# Sheet1.net
KiCad netlist of a schematic drawn in Altium Designer
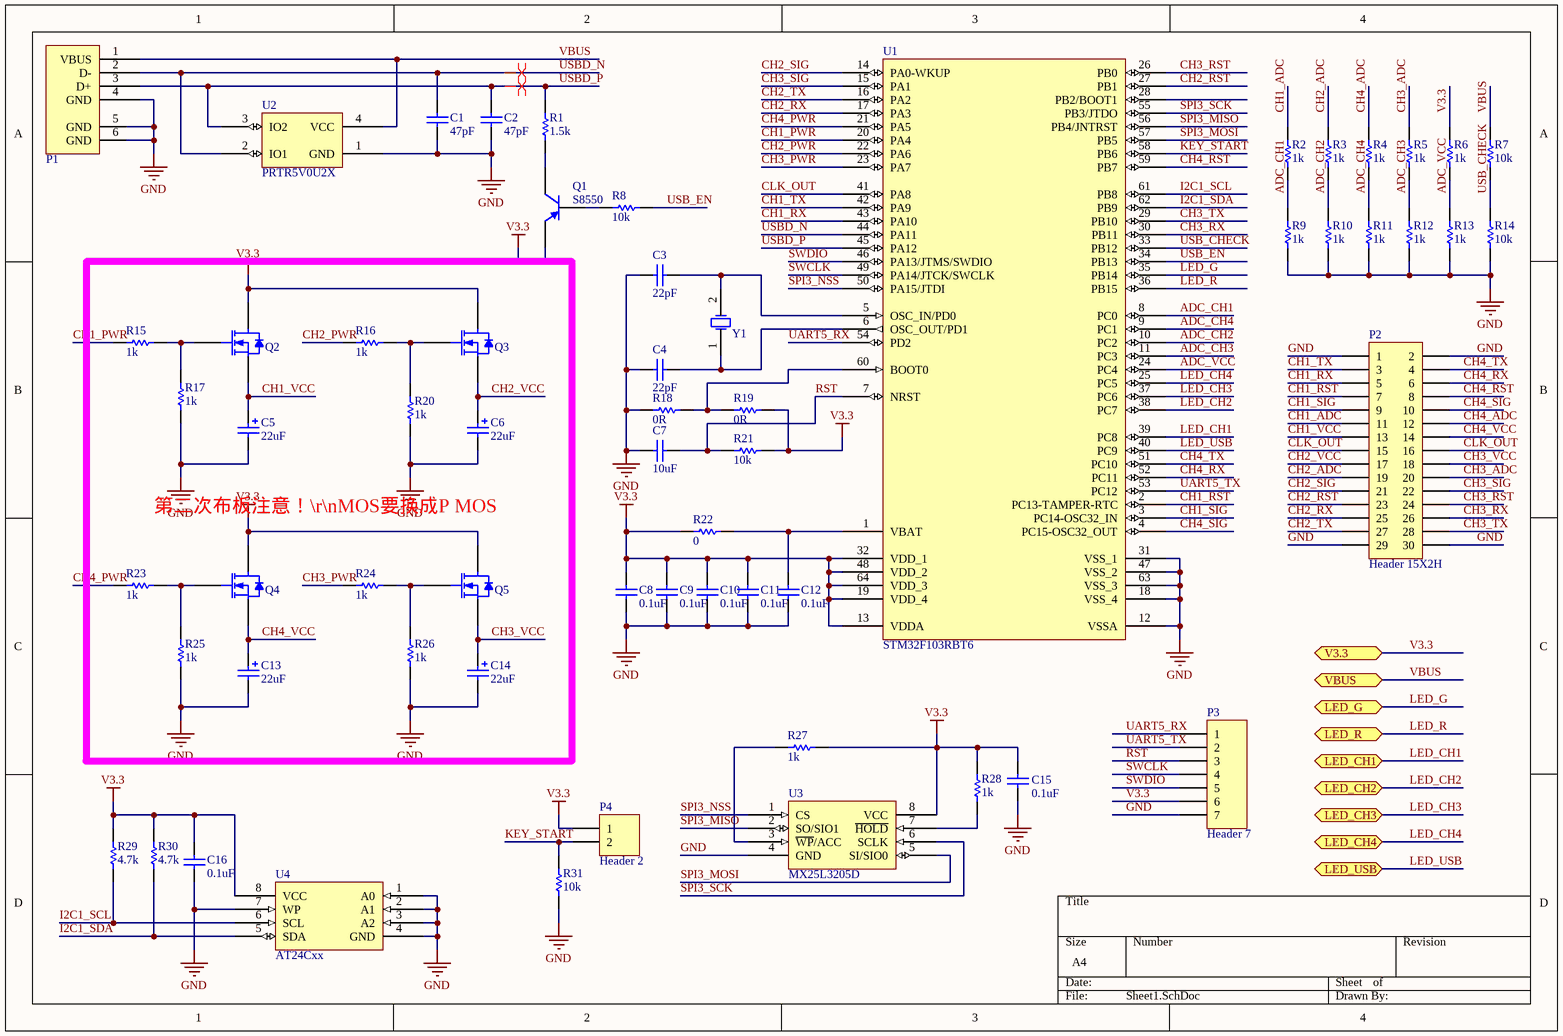
[diagram p0: Sheet1.SchDoc]

(export (version "E")
  (design (tool "Eeschema 10.0.6"))
  (components
    (comp (ref "C1")
      (value "47pF")
      (footprint "0805")
      (fields (field (name "Comment") "Cap"))
      (libsource (lib "SelfLib") (part "Cap"))
    )
    (comp (ref "C2")
      (value "47pF")
      (footprint "0805")
      (fields (field (name "Comment") "Cap"))
      (libsource (lib "SelfLib") (part "Cap"))
    )
    (comp (ref "C3")
      (value "22pF")
      (footprint "0805")
      (fields (field (name "Comment") "Cap"))
      (libsource (lib "SelfLib") (part "Cap"))
    )
    (comp (ref "C4")
      (value "22pF")
      (footprint "0805")
      (fields (field (name "Comment") "Cap"))
      (libsource (lib "SelfLib") (part "Cap"))
    )
    (comp (ref "C5")
      (value "22uF")
      (footprint "0805A")
      (fields (field (name "Comment") "Cap"))
      (libsource (lib "SelfLib") (part "Cap Pol"))
    )
    (comp (ref "C6")
      (value "22uF")
      (footprint "0805A")
      (fields (field (name "Comment") "Cap"))
      (libsource (lib "SelfLib") (part "Cap Pol"))
    )
    (comp (ref "C7")
      (value "10uF")
      (footprint "0805")
      (fields (field (name "Comment") "Cap"))
      (libsource (lib "SelfLib") (part "Cap"))
    )
    (comp (ref "C8")
      (value "0.1uF")
      (footprint "0805")
      (fields (field (name "Comment") "Cap"))
      (libsource (lib "SelfLib") (part "Cap"))
    )
    (comp (ref "C9")
      (value "0.1uF")
      (footprint "0805")
      (fields (field (name "Comment") "Cap"))
      (libsource (lib "SelfLib") (part "Cap"))
    )
    (comp (ref "C10")
      (value "0.1uF")
      (footprint "0805")
      (fields (field (name "Comment") "Cap"))
      (libsource (lib "SelfLib") (part "Cap"))
    )
    (comp (ref "C11")
      (value "0.1uF")
      (footprint "0805")
      (fields (field (name "Comment") "Cap"))
      (libsource (lib "SelfLib") (part "Cap"))
    )
    (comp (ref "C12")
      (value "0.1uF")
      (footprint "0805")
      (fields (field (name "Comment") "Cap"))
      (libsource (lib "SelfLib") (part "Cap"))
    )
    (comp (ref "C13")
      (value "22uF")
      (footprint "0805A")
      (fields (field (name "Comment") "Cap"))
      (libsource (lib "SelfLib") (part "Cap Pol"))
    )
    (comp (ref "C14")
      (value "22uF")
      (footprint "0805A")
      (fields (field (name "Comment") "Cap"))
      (libsource (lib "SelfLib") (part "Cap Pol"))
    )
    (comp (ref "C15")
      (value "0.1uF")
      (footprint "0805")
      (fields (field (name "Comment") "Cap"))
      (libsource (lib "SelfLib") (part "Cap"))
    )
    (comp (ref "C16")
      (value "0.1uF")
      (footprint "0805")
      (fields (field (name "Comment") "Cap"))
      (libsource (lib "SelfLib") (part "Cap"))
    )
    (comp (ref "P1") (value "USB") (footprint "USB_B_FE") (libsource (lib "SelfLib") (part "USB Socket")))
    (comp (ref "P2")
      (value "Header 15X2H")
      (footprint "HDR2X15H")
      (description "Header, 15-Pin, Dual row, Right Angle")
      (fields (field (name "PUBLISHER") "Altium Limited"))
      (libsource (lib "Miscellaneous Connectors") (part "Header 15X2H"))
    )
    (comp (ref "P3")
      (value "Header 7")
      (footprint "HDR1X7")
      (description "Header, 7-Pin")
      (fields (field (name "PUBLISHER") "Altium Limited"))
      (libsource (lib "Miscellaneous Connectors") (part "Header 7"))
    )
    (comp (ref "P4")
      (value "Header 2")
      (footprint "HDR1X2")
      (description "Header, 2-Pin")
      (fields (field (name "PUBLISHER") "Altium Limited"))
      (libsource (lib "Miscellaneous Connectors") (part "Header 2"))
    )
    (comp (ref "Q1") (value "S8550") (footprint "SOT-23") (libsource (lib "SelfLib") (part "S8550")))
    (comp (ref "Q2") (value "N-MOS") (footprint "SOT-23") (libsource (lib "SelfLib") (part "N-MOS")))
    (comp (ref "Q3") (value "N-MOS") (footprint "SOT-23") (libsource (lib "SelfLib") (part "N-MOS")))
    (comp (ref "Q4") (value "N-MOS") (footprint "SOT-23") (libsource (lib "SelfLib") (part "N-MOS")))
    (comp (ref "Q5") (value "N-MOS") (footprint "SOT-23") (libsource (lib "SelfLib") (part "N-MOS")))
    (comp (ref "R1")
      (value "1.5k")
      (footprint "0805")
      (fields (field (name "Comment") "Res"))
      (libsource (lib "SelfLib") (part "Res"))
    )
    (comp (ref "R2")
      (value "1k")
      (footprint "0805")
      (fields (field (name "Comment") "Res"))
      (libsource (lib "SelfLib") (part "Res"))
    )
    (comp (ref "R3")
      (value "1k")
      (footprint "0805")
      (fields (field (name "Comment") "Res"))
      (libsource (lib "SelfLib") (part "Res"))
    )
    (comp (ref "R4")
      (value "1k")
      (footprint "0805")
      (fields (field (name "Comment") "Res"))
      (libsource (lib "SelfLib") (part "Res"))
    )
    (comp (ref "R5")
      (value "1k")
      (footprint "0805")
      (fields (field (name "Comment") "Res"))
      (libsource (lib "SelfLib") (part "Res"))
    )
    (comp (ref "R6")
      (value "1k")
      (footprint "0805")
      (fields (field (name "Comment") "Res"))
      (libsource (lib "SelfLib") (part "Res"))
    )
    (comp (ref "R7")
      (value "10k")
      (footprint "0805")
      (fields (field (name "Comment") "Res"))
      (libsource (lib "SelfLib") (part "Res"))
    )
    (comp (ref "R8")
      (value "10k")
      (footprint "0805")
      (fields (field (name "Comment") "Res"))
      (libsource (lib "SelfLib") (part "Res"))
    )
    (comp (ref "R9")
      (value "1k")
      (footprint "0805")
      (fields (field (name "Comment") "Res"))
      (libsource (lib "SelfLib") (part "Res"))
    )
    (comp (ref "R10")
      (value "1k")
      (footprint "0805")
      (fields (field (name "Comment") "Res"))
      (libsource (lib "SelfLib") (part "Res"))
    )
    (comp (ref "R11")
      (value "1k")
      (footprint "0805")
      (fields (field (name "Comment") "Res"))
      (libsource (lib "SelfLib") (part "Res"))
    )
    (comp (ref "R12")
      (value "1k")
      (footprint "0805")
      (fields (field (name "Comment") "Res"))
      (libsource (lib "SelfLib") (part "Res"))
    )
    (comp (ref "R13")
      (value "1k")
      (footprint "0805")
      (fields (field (name "Comment") "Res"))
      (libsource (lib "SelfLib") (part "Res"))
    )
    (comp (ref "R14")
      (value "10k")
      (footprint "0805")
      (fields (field (name "Comment") "Res"))
      (libsource (lib "SelfLib") (part "Res"))
    )
    (comp (ref "R15")
      (value "1k")
      (footprint "0805")
      (fields (field (name "Comment") "Res"))
      (libsource (lib "SelfLib") (part "Res"))
    )
    (comp (ref "R16")
      (value "1k")
      (footprint "0805")
      (fields (field (name "Comment") "Res"))
      (libsource (lib "SelfLib") (part "Res"))
    )
    (comp (ref "R17")
      (value "1k")
      (footprint "0805")
      (fields (field (name "Comment") "Res"))
      (libsource (lib "SelfLib") (part "Res"))
    )
    (comp (ref "R18")
      (value "0R")
      (footprint "0805")
      (fields (field (name "Comment") "Res"))
      (libsource (lib "SelfLib") (part "Res"))
    )
    (comp (ref "R19")
      (value "0R")
      (footprint "0805")
      (fields (field (name "Comment") "Res"))
      (libsource (lib "SelfLib") (part "Res"))
    )
    (comp (ref "R20")
      (value "1k")
      (footprint "0805")
      (fields (field (name "Comment") "Res"))
      (libsource (lib "SelfLib") (part "Res"))
    )
    (comp (ref "R21")
      (value "10k")
      (footprint "0805")
      (fields (field (name "Comment") "Res"))
      (libsource (lib "SelfLib") (part "Res"))
    )
    (comp (ref "R22")
      (value "0")
      (footprint "0805")
      (fields (field (name "Comment") "Res"))
      (libsource (lib "SelfLib") (part "Res"))
    )
    (comp (ref "R23")
      (value "1k")
      (footprint "0805")
      (fields (field (name "Comment") "Res"))
      (libsource (lib "SelfLib") (part "Res"))
    )
    (comp (ref "R24")
      (value "1k")
      (footprint "0805")
      (fields (field (name "Comment") "Res"))
      (libsource (lib "SelfLib") (part "Res"))
    )
    (comp (ref "R25")
      (value "1k")
      (footprint "0805")
      (fields (field (name "Comment") "Res"))
      (libsource (lib "SelfLib") (part "Res"))
    )
    (comp (ref "R26")
      (value "1k")
      (footprint "0805")
      (fields (field (name "Comment") "Res"))
      (libsource (lib "SelfLib") (part "Res"))
    )
    (comp (ref "R27")
      (value "1k")
      (footprint "0805")
      (fields (field (name "Comment") "Res"))
      (libsource (lib "SelfLib") (part "Res"))
    )
    (comp (ref "R28")
      (value "1k")
      (footprint "0805")
      (fields (field (name "Comment") "Res"))
      (libsource (lib "SelfLib") (part "Res"))
    )
    (comp (ref "R29")
      (value "4.7k")
      (footprint "0805")
      (fields (field (name "Comment") "Res"))
      (libsource (lib "SelfLib") (part "Res"))
    )
    (comp (ref "R30")
      (value "4.7k")
      (footprint "0805")
      (fields (field (name "Comment") "Res"))
      (libsource (lib "SelfLib") (part "Res"))
    )
    (comp (ref "R31")
      (value "10k")
      (footprint "0805")
      (fields (field (name "Comment") "Res"))
      (libsource (lib "SelfLib") (part "Res"))
    )
    (comp (ref "U1")
      (value "STM32F103RBT6")
      (footprint "LQFP64_M")
      (description "STM32 ARM-based 32-bit MCU with 128 Kbytes Flash, 64-pin LQFP, Industrial Temperature")
      (fields (field (name "PUBLISHER") "Altium Limited"))
      (libsource (lib "ST Microcontroller 32-Bit STM32") (part "STM32F103RBT6"))
    )
    (comp (ref "U2")
      (value "PRTR5V0U2X")
      (footprint "SOT143B")
      (libsource (lib "SelfLib") (part "PRTR5V0U2X"))
    )
    (comp (ref "U3")
      (value "MX25L3205D")
      (footprint "SOP-8")
      (libsource (lib "SelfLib") (part "MX25L1605D/MX25L3205D/MX25L6405D"))
    )
    (comp (ref "U4") (value "AT24Cxx") (footprint "SOP-8") (libsource (lib "SelfLib") (part "AT24Cxx")))
    (comp (ref "Y1") (value "XTAL2") (footprint "SP_XTAL") (libsource (lib "SelfLib") (part "XTAL2")))
  )
  (nets
    (net (code "1") (name "/ADC_CH1") (class "Default")
      (node (ref "R2") (pin "1") (pinfunction "1_1") (pintype "passive"))
      (node (ref "R9") (pin "2") (pinfunction "2_2") (pintype "passive"))
      (node (ref "U1") (pin "8") (pinfunction "PC0_8") (pintype "bidirectional"))
    )
    (net (code "2") (name "/ADC_CH2") (class "Default")
      (node (ref "R10") (pin "2") (pinfunction "2_2") (pintype "passive"))
      (node (ref "R3") (pin "1") (pinfunction "1_1") (pintype "passive"))
      (node (ref "U1") (pin "10") (pinfunction "PC2_10") (pintype "bidirectional"))
    )
    (net (code "3") (name "/ADC_CH3") (class "Default")
      (node (ref "R12") (pin "2") (pinfunction "2_2") (pintype "passive"))
      (node (ref "R5") (pin "1") (pinfunction "1_1") (pintype "passive"))
      (node (ref "U1") (pin "11") (pinfunction "PC3_11") (pintype "bidirectional"))
    )
    (net (code "4") (name "/ADC_CH4") (class "Default")
      (node (ref "R11") (pin "2") (pinfunction "2_2") (pintype "passive"))
      (node (ref "R4") (pin "1") (pinfunction "1_1") (pintype "passive"))
      (node (ref "U1") (pin "9") (pinfunction "PC1_9") (pintype "bidirectional"))
    )
    (net (code "5") (name "/ADC_VCC") (class "Default")
      (node (ref "R13") (pin "2") (pinfunction "2_2") (pintype "passive"))
      (node (ref "R6") (pin "1") (pinfunction "1_1") (pintype "passive"))
      (node (ref "U1") (pin "24") (pinfunction "PC4_24") (pintype "bidirectional"))
    )
    (net (code "6") (name "/CH1_ADC") (class "Default")
      (node (ref "P2") (pin "11") (pinfunction "11_11") (pintype "passive"))
      (node (ref "R2") (pin "2") (pinfunction "2_2") (pintype "passive"))
    )
    (net (code "7") (name "/CH1_PWR") (class "Default")
      (node (ref "R15") (pin "1") (pinfunction "1_1") (pintype "passive"))
      (node (ref "U1") (pin "20") (pinfunction "PA4_20") (pintype "bidirectional"))
    )
    (net (code "8") (name "/CH1_RST") (class "Default")
      (node (ref "P2") (pin "7") (pinfunction "7_7") (pintype "passive"))
      (node (ref "U1") (pin "2") (pinfunction "PC13-TAMPER-RTC_2") (pintype "bidirectional"))
    )
    (net (code "9") (name "/CH1_RX") (class "Default")
      (node (ref "P2") (pin "5") (pinfunction "5_5") (pintype "passive"))
      (node (ref "U1") (pin "43") (pinfunction "PA10_43") (pintype "bidirectional"))
    )
    (net (code "10") (name "/CH1_SIG") (class "Default")
      (node (ref "P2") (pin "9") (pinfunction "9_9") (pintype "passive"))
      (node (ref "U1") (pin "3") (pinfunction "PC14-OSC32_IN_3") (pintype "bidirectional"))
    )
    (net (code "11") (name "/CH1_TX") (class "Default")
      (node (ref "P2") (pin "3") (pinfunction "3_3") (pintype "passive"))
      (node (ref "U1") (pin "42") (pinfunction "PA9_42") (pintype "bidirectional"))
    )
    (net (code "12") (name "/CH1_VCC") (class "Default")
      (node (ref "C5") (pin "1") (pinfunction "1_1") (pintype "passive"))
      (node (ref "P2") (pin "13") (pinfunction "13_13") (pintype "passive"))
      (node (ref "Q2") (pin "2") (pinfunction "S_2") (pintype "passive"))
    )
    (net (code "13") (name "/CH2_ADC") (class "Default")
      (node (ref "P2") (pin "19") (pinfunction "19_19") (pintype "passive"))
      (node (ref "R3") (pin "2") (pinfunction "2_2") (pintype "passive"))
    )
    (net (code "14") (name "/CH2_PWR") (class "Default")
      (node (ref "R16") (pin "2") (pinfunction "2_2") (pintype "passive"))
      (node (ref "U1") (pin "22") (pinfunction "PA6_22") (pintype "bidirectional"))
    )
    (net (code "15") (name "/CH2_RST") (class "Default")
      (node (ref "P2") (pin "23") (pinfunction "23_23") (pintype "passive"))
      (node (ref "U1") (pin "27") (pinfunction "PB1_27") (pintype "bidirectional"))
    )
    (net (code "16") (name "/CH2_RX") (class "Default")
      (node (ref "P2") (pin "25") (pinfunction "25_25") (pintype "passive"))
      (node (ref "U1") (pin "17") (pinfunction "PA3_17") (pintype "bidirectional"))
    )
    (net (code "17") (name "/CH2_SIG") (class "Default")
      (node (ref "P2") (pin "21") (pinfunction "21_21") (pintype "passive"))
      (node (ref "U1") (pin "14") (pinfunction "PA0-WKUP_14") (pintype "bidirectional"))
    )
    (net (code "18") (name "/CH2_TX") (class "Default")
      (node (ref "P2") (pin "27") (pinfunction "27_27") (pintype "passive"))
      (node (ref "U1") (pin "16") (pinfunction "PA2_16") (pintype "bidirectional"))
    )
    (net (code "19") (name "/CH2_VCC") (class "Default")
      (node (ref "C6") (pin "1") (pinfunction "1_1") (pintype "passive"))
      (node (ref "P2") (pin "17") (pinfunction "17_17") (pintype "passive"))
      (node (ref "Q3") (pin "2") (pinfunction "S_2") (pintype "passive"))
    )
    (net (code "20") (name "/CH3_ADC") (class "Default")
      (node (ref "P2") (pin "20") (pinfunction "20_20") (pintype "passive"))
      (node (ref "R5") (pin "2") (pinfunction "2_2") (pintype "passive"))
    )
    (net (code "21") (name "/CH3_PWR") (class "Default")
      (node (ref "R24") (pin "2") (pinfunction "2_2") (pintype "passive"))
      (node (ref "U1") (pin "23") (pinfunction "PA7_23") (pintype "bidirectional"))
    )
    (net (code "22") (name "/CH3_RST") (class "Default")
      (node (ref "P2") (pin "24") (pinfunction "24_24") (pintype "passive"))
      (node (ref "U1") (pin "26") (pinfunction "PB0_26") (pintype "bidirectional"))
    )
    (net (code "23") (name "/CH3_RX") (class "Default")
      (node (ref "P2") (pin "26") (pinfunction "26_26") (pintype "passive"))
      (node (ref "U1") (pin "30") (pinfunction "PB11_30") (pintype "bidirectional"))
    )
    (net (code "24") (name "/CH3_SIG") (class "Default")
      (node (ref "P2") (pin "22") (pinfunction "22_22") (pintype "passive"))
      (node (ref "U1") (pin "15") (pinfunction "PA1_15") (pintype "bidirectional"))
    )
    (net (code "25") (name "/CH3_TX") (class "Default")
      (node (ref "P2") (pin "28") (pinfunction "28_28") (pintype "passive"))
      (node (ref "U1") (pin "29") (pinfunction "PB10_29") (pintype "bidirectional"))
    )
    (net (code "26") (name "/CH3_VCC") (class "Default")
      (node (ref "C14") (pin "1") (pinfunction "1_1") (pintype "passive"))
      (node (ref "P2") (pin "18") (pinfunction "18_18") (pintype "passive"))
      (node (ref "Q5") (pin "2") (pinfunction "S_2") (pintype "passive"))
    )
    (net (code "27") (name "/CH4_ADC") (class "Default")
      (node (ref "P2") (pin "12") (pinfunction "12_12") (pintype "passive"))
      (node (ref "R4") (pin "2") (pinfunction "2_2") (pintype "passive"))
    )
    (net (code "28") (name "/CH4_PWR") (class "Default")
      (node (ref "R23") (pin "1") (pinfunction "1_1") (pintype "passive"))
      (node (ref "U1") (pin "21") (pinfunction "PA5_21") (pintype "bidirectional"))
    )
    (net (code "29") (name "/CH4_RST") (class "Default")
      (node (ref "P2") (pin "8") (pinfunction "8_8") (pintype "passive"))
      (node (ref "U1") (pin "59") (pinfunction "PB7_59") (pintype "bidirectional"))
    )
    (net (code "30") (name "/CH4_RX") (class "Default")
      (node (ref "P2") (pin "6") (pinfunction "6_6") (pintype "passive"))
      (node (ref "U1") (pin "52") (pinfunction "PC11_52") (pintype "bidirectional"))
    )
    (net (code "31") (name "/CH4_SIG") (class "Default")
      (node (ref "P2") (pin "10") (pinfunction "10_10") (pintype "passive"))
      (node (ref "U1") (pin "4") (pinfunction "PC15-OSC32_OUT_4") (pintype "bidirectional"))
    )
    (net (code "32") (name "/CH4_TX") (class "Default")
      (node (ref "P2") (pin "4") (pinfunction "4_4") (pintype "passive"))
      (node (ref "U1") (pin "51") (pinfunction "PC10_51") (pintype "bidirectional"))
    )
    (net (code "33") (name "/CH4_VCC") (class "Default")
      (node (ref "C13") (pin "1") (pinfunction "1_1") (pintype "passive"))
      (node (ref "P2") (pin "14") (pinfunction "14_14") (pintype "passive"))
      (node (ref "Q4") (pin "2") (pinfunction "S_2") (pintype "passive"))
    )
    (net (code "34") (name "/CLK_OUT") (class "Default")
      (node (ref "P2") (pin "15") (pinfunction "15_15") (pintype "passive"))
      (node (ref "P2") (pin "16") (pinfunction "16_16") (pintype "passive"))
      (node (ref "U1") (pin "41") (pinfunction "PA8_41") (pintype "bidirectional"))
    )
    (net (code "35") (name "/I2C1_SCL") (class "Default")
      (node (ref "R29") (pin "1") (pinfunction "1_1") (pintype "passive"))
      (node (ref "U1") (pin "61") (pinfunction "PB8_61") (pintype "bidirectional"))
      (node (ref "U4") (pin "6") (pinfunction "SCL_6") (pintype "input"))
    )
    (net (code "36") (name "/I2C1_SDA") (class "Default")
      (node (ref "R30") (pin "1") (pinfunction "1_1") (pintype "passive"))
      (node (ref "U1") (pin "62") (pinfunction "PB9_62") (pintype "bidirectional"))
      (node (ref "U4") (pin "5") (pinfunction "SDA_5") (pintype "bidirectional"))
    )
    (net (code "37") (name "/KEY_START") (class "Default")
      (node (ref "P4") (pin "2") (pinfunction "2_2") (pintype "passive"))
      (node (ref "R31") (pin "2") (pinfunction "2_2") (pintype "passive"))
      (node (ref "U1") (pin "58") (pinfunction "PB6_58") (pintype "bidirectional"))
    )
    (net (code "38") (name "/LED_CH1") (class "Default")
      (node (ref "U1") (pin "39") (pinfunction "PC8_39") (pintype "bidirectional"))
    )
    (net (code "39") (name "/LED_CH2") (class "Default")
      (node (ref "U1") (pin "38") (pinfunction "PC7_38") (pintype "bidirectional"))
    )
    (net (code "40") (name "/LED_CH3") (class "Default")
      (node (ref "U1") (pin "37") (pinfunction "PC6_37") (pintype "bidirectional"))
    )
    (net (code "41") (name "/LED_CH4") (class "Default")
      (node (ref "U1") (pin "25") (pinfunction "PC5_25") (pintype "bidirectional"))
    )
    (net (code "42") (name "/LED_G") (class "Default")
      (node (ref "U1") (pin "35") (pinfunction "PB14_35") (pintype "bidirectional"))
    )
    (net (code "43") (name "/LED_R") (class "Default")
      (node (ref "U1") (pin "36") (pinfunction "PB15_36") (pintype "bidirectional"))
    )
    (net (code "44") (name "/LED_USB") (class "Default")
      (node (ref "U1") (pin "40") (pinfunction "PC9_40") (pintype "bidirectional"))
    )
    (net (code "45") (name "/RST") (class "Default")
      (node (ref "C7") (pin "1") (pinfunction "1_1") (pintype "passive"))
      (node (ref "P3") (pin "3") (pinfunction "3_3") (pintype "passive"))
      (node (ref "R21") (pin "2") (pinfunction "2_2") (pintype "passive"))
      (node (ref "U1") (pin "7") (pinfunction "NRST_7") (pintype "bidirectional"))
    )
    (net (code "46") (name "/SPI3_MISO") (class "Default")
      (node (ref "U1") (pin "56") (pinfunction "PB4/JNTRST_56") (pintype "bidirectional"))
      (node (ref "U3") (pin "2") (pinfunction "SO/SIO1_2") (pintype "bidirectional"))
    )
    (net (code "47") (name "/SPI3_MOSI") (class "Default")
      (node (ref "U1") (pin "57") (pinfunction "PB5_57") (pintype "bidirectional"))
      (node (ref "U3") (pin "5") (pinfunction "SI/SIO0_5") (pintype "bidirectional"))
    )
    (net (code "48") (name "/SPI3_NSS") (class "Default")
      (node (ref "U1") (pin "50") (pinfunction "PA15/JTDI_50") (pintype "bidirectional"))
      (node (ref "U3") (pin "1") (pinfunction "CS_1") (pintype "input"))
    )
    (net (code "49") (name "/SPI3_SCK") (class "Default")
      (node (ref "U1") (pin "55") (pinfunction "PB3/JTDO_55") (pintype "bidirectional"))
      (node (ref "U3") (pin "6") (pinfunction "SCLK_6") (pintype "input"))
    )
    (net (code "50") (name "/SWCLK") (class "Default")
      (node (ref "P3") (pin "4") (pinfunction "4_4") (pintype "passive"))
      (node (ref "U1") (pin "49") (pinfunction "PA14/JTCK/SWCLK_49") (pintype "bidirectional"))
    )
    (net (code "51") (name "/SWDIO") (class "Default")
      (node (ref "P3") (pin "5") (pinfunction "5_5") (pintype "passive"))
      (node (ref "U1") (pin "46") (pinfunction "PA13/JTMS/SWDIO_46") (pintype "bidirectional"))
    )
    (net (code "52") (name "/UART5_RX") (class "Default")
      (node (ref "P3") (pin "1") (pinfunction "1_1") (pintype "passive"))
      (node (ref "U1") (pin "54") (pinfunction "PD2_54") (pintype "bidirectional"))
    )
    (net (code "53") (name "/UART5_TX") (class "Default")
      (node (ref "P3") (pin "2") (pinfunction "2_2") (pintype "passive"))
      (node (ref "U1") (pin "53") (pinfunction "PC12_53") (pintype "bidirectional"))
    )
    (net (code "54") (name "/USBD_N") (class "Default")
      (node (ref "C1") (pin "2") (pinfunction "2_2") (pintype "passive"))
      (node (ref "P1") (pin "2") (pinfunction "D-_2") (pintype "passive"))
      (node (ref "U1") (pin "44") (pinfunction "PA11_44") (pintype "bidirectional"))
      (node (ref "U2") (pin "2") (pinfunction "IO1_2") (pintype "bidirectional"))
    )
    (net (code "55") (name "/USBD_P") (class "Default")
      (node (ref "C2") (pin "2") (pinfunction "2_2") (pintype "passive"))
      (node (ref "P1") (pin "3") (pinfunction "D+_3") (pintype "passive"))
      (node (ref "R1") (pin "2") (pinfunction "2_2") (pintype "passive"))
      (node (ref "U1") (pin "45") (pinfunction "PA12_45") (pintype "bidirectional"))
      (node (ref "U2") (pin "3") (pinfunction "IO2_3") (pintype "bidirectional"))
    )
    (net (code "56") (name "/USB_CHECK") (class "Default")
      (node (ref "R14") (pin "2") (pinfunction "2_2") (pintype "passive"))
      (node (ref "R7") (pin "1") (pinfunction "1_1") (pintype "passive"))
      (node (ref "U1") (pin "33") (pinfunction "PB12_33") (pintype "bidirectional"))
    )
    (net (code "57") (name "/USB_EN") (class "Default")
      (node (ref "R8") (pin "2") (pinfunction "2_2") (pintype "passive"))
      (node (ref "U1") (pin "34") (pinfunction "PB13_34") (pintype "bidirectional"))
    )
    (net (code "58") (name "/VBUS") (class "Default")
      (node (ref "P1") (pin "1") (pinfunction "VBUS_1") (pintype "passive"))
      (node (ref "R7") (pin "2") (pinfunction "2_2") (pintype "passive"))
      (node (ref "U2") (pin "4") (pinfunction "VCC_4") (pintype "power_in"))
    )
    (net (code "59") (name "GND") (class "Default")
      (node (ref "C1") (pin "1") (pinfunction "1_1") (pintype "passive"))
      (node (ref "C10") (pin "1") (pinfunction "1_1") (pintype "passive"))
      (node (ref "C11") (pin "1") (pinfunction "1_1") (pintype "passive"))
      (node (ref "C12") (pin "1") (pinfunction "1_1") (pintype "passive"))
      (node (ref "C13") (pin "2") (pinfunction "2_2") (pintype "passive"))
      (node (ref "C14") (pin "2") (pinfunction "2_2") (pintype "passive"))
      (node (ref "C15") (pin "1") (pinfunction "1_1") (pintype "passive"))
      (node (ref "C16") (pin "1") (pinfunction "1_1") (pintype "passive"))
      (node (ref "C2") (pin "1") (pinfunction "1_1") (pintype "passive"))
      (node (ref "C3") (pin "1") (pinfunction "1_1") (pintype "passive"))
      (node (ref "C4") (pin "2") (pinfunction "2_2") (pintype "passive"))
      (node (ref "C5") (pin "2") (pinfunction "2_2") (pintype "passive"))
      (node (ref "C6") (pin "2") (pinfunction "2_2") (pintype "passive"))
      (node (ref "C7") (pin "2") (pinfunction "2_2") (pintype "passive"))
      (node (ref "C8") (pin "1") (pinfunction "1_1") (pintype "passive"))
      (node (ref "C9") (pin "1") (pinfunction "1_1") (pintype "passive"))
      (node (ref "P1") (pin "4") (pinfunction "GND_4") (pintype "passive"))
      (node (ref "P1") (pin "5") (pinfunction "GND_5") (pintype "passive"))
      (node (ref "P1") (pin "6") (pinfunction "GND_6") (pintype "passive"))
      (node (ref "P2") (pin "1") (pinfunction "1_1") (pintype "passive"))
      (node (ref "P2") (pin "2") (pinfunction "2_2") (pintype "passive"))
      (node (ref "P2") (pin "29") (pinfunction "29_29") (pintype "passive"))
      (node (ref "P2") (pin "30") (pinfunction "30_30") (pintype "passive"))
      (node (ref "P3") (pin "7") (pinfunction "7_7") (pintype "passive"))
      (node (ref "R10") (pin "1") (pinfunction "1_1") (pintype "passive"))
      (node (ref "R11") (pin "1") (pinfunction "1_1") (pintype "passive"))
      (node (ref "R12") (pin "1") (pinfunction "1_1") (pintype "passive"))
      (node (ref "R13") (pin "1") (pinfunction "1_1") (pintype "passive"))
      (node (ref "R14") (pin "1") (pinfunction "1_1") (pintype "passive"))
      (node (ref "R17") (pin "1") (pinfunction "1_1") (pintype "passive"))
      (node (ref "R18") (pin "1") (pinfunction "1_1") (pintype "passive"))
      (node (ref "R20") (pin "2") (pinfunction "2_2") (pintype "passive"))
      (node (ref "R25") (pin "1") (pinfunction "1_1") (pintype "passive"))
      (node (ref "R26") (pin "2") (pinfunction "2_2") (pintype "passive"))
      (node (ref "R31") (pin "1") (pinfunction "1_1") (pintype "passive"))
      (node (ref "R9") (pin "1") (pinfunction "1_1") (pintype "passive"))
      (node (ref "U1") (pin "12") (pinfunction "VSSA_12") (pintype "power_in"))
      (node (ref "U1") (pin "18") (pinfunction "VSS_4_18") (pintype "power_in"))
      (node (ref "U1") (pin "31") (pinfunction "VSS_1_31") (pintype "power_in"))
      (node (ref "U1") (pin "47") (pinfunction "VSS_2_47") (pintype "power_in"))
      (node (ref "U1") (pin "63") (pinfunction "VSS_3_63") (pintype "power_in"))
      (node (ref "U2") (pin "1") (pinfunction "GND_1") (pintype "power_in"))
      (node (ref "U3") (pin "4") (pinfunction "GND_4") (pintype "power_in"))
      (node (ref "U4") (pin "1") (pinfunction "A0_1") (pintype "input"))
      (node (ref "U4") (pin "2") (pinfunction "A1_2") (pintype "input"))
      (node (ref "U4") (pin "3") (pinfunction "A2_3") (pintype "input"))
      (node (ref "U4") (pin "4") (pinfunction "GND_4") (pintype "power_in"))
      (node (ref "U4") (pin "7") (pinfunction "WP_7") (pintype "input"))
    )
    (net (code "60") (name "Net-(Q1-B)") (class "Default")
      (node (ref "Q1") (pin "1") (pinfunction "B_1") (pintype "passive"))
      (node (ref "R8") (pin "1") (pinfunction "1_1") (pintype "passive"))
    )
    (net (code "61") (name "Net-(Q1-C)") (class "Default")
      (node (ref "Q1") (pin "3") (pinfunction "C_3") (pintype "passive"))
      (node (ref "R1") (pin "1") (pinfunction "1_1") (pintype "passive"))
    )
    (net (code "62") (name "Net-(Q2-G)") (class "Default")
      (node (ref "Q2") (pin "1") (pinfunction "G_1") (pintype "passive"))
      (node (ref "R15") (pin "2") (pinfunction "2_2") (pintype "passive"))
      (node (ref "R17") (pin "2") (pinfunction "2_2") (pintype "passive"))
    )
    (net (code "63") (name "Net-(Q3-G)") (class "Default")
      (node (ref "Q3") (pin "1") (pinfunction "G_1") (pintype "passive"))
      (node (ref "R16") (pin "1") (pinfunction "1_1") (pintype "passive"))
      (node (ref "R20") (pin "1") (pinfunction "1_1") (pintype "passive"))
    )
    (net (code "64") (name "Net-(Q4-G)") (class "Default")
      (node (ref "Q4") (pin "1") (pinfunction "G_1") (pintype "passive"))
      (node (ref "R23") (pin "2") (pinfunction "2_2") (pintype "passive"))
      (node (ref "R25") (pin "2") (pinfunction "2_2") (pintype "passive"))
    )
    (net (code "65") (name "Net-(Q5-G)") (class "Default")
      (node (ref "Q5") (pin "1") (pinfunction "G_1") (pintype "passive"))
      (node (ref "R24") (pin "1") (pinfunction "1_1") (pintype "passive"))
      (node (ref "R26") (pin "1") (pinfunction "1_1") (pintype "passive"))
    )
    (net (code "66") (name "Net-(U1-BOOT0)") (class "Default")
      (node (ref "R18") (pin "2") (pinfunction "2_2") (pintype "passive"))
      (node (ref "R19") (pin "1") (pinfunction "1_1") (pintype "passive"))
      (node (ref "U1") (pin "60") (pinfunction "BOOT0_60") (pintype "input"))
    )
    (net (code "67") (name "Net-(U1-OSC_IN{slash}PD0)") (class "Default")
      (node (ref "C3") (pin "2") (pinfunction "2_2") (pintype "passive"))
      (node (ref "U1") (pin "5") (pinfunction "OSC_IN/PD0_5") (pintype "input"))
      (node (ref "Y1") (pin "2") (pinfunction "OSC2_2") (pintype "passive"))
    )
    (net (code "68") (name "Net-(U1-OSC_OUT{slash}PD1)") (class "Default")
      (node (ref "C4") (pin "1") (pinfunction "1_1") (pintype "passive"))
      (node (ref "U1") (pin "6") (pinfunction "OSC_OUT/PD1_6") (pintype "output"))
      (node (ref "Y1") (pin "1") (pinfunction "OSC1_1") (pintype "passive"))
    )
    (net (code "69") (name "Net-(U1-VBAT)") (class "Default")
      (node (ref "C12") (pin "2") (pinfunction "2_2") (pintype "passive"))
      (node (ref "R22") (pin "2") (pinfunction "2_2") (pintype "passive"))
      (node (ref "U1") (pin "1") (pinfunction "VBAT_1") (pintype "power_in"))
    )
    (net (code "70") (name "Net-(U3-~{HOLD})") (class "Default")
      (node (ref "R28") (pin "1") (pinfunction "1_1") (pintype "passive"))
      (node (ref "U3") (pin "7") (pinfunction "~{HOLD}_7") (pintype "input"))
    )
    (net (code "71") (name "Net-(U3-~{WP}{slash}ACC)") (class "Default")
      (node (ref "R27") (pin "1") (pinfunction "1_1") (pintype "passive"))
      (node (ref "U3") (pin "3") (pinfunction "~{WP}/ACC_3") (pintype "input"))
    )
    (net (code "72") (name "V3.3") (class "Default")
      (node (ref "C10") (pin "2") (pinfunction "2_2") (pintype "passive"))
      (node (ref "C11") (pin "2") (pinfunction "2_2") (pintype "passive"))
      (node (ref "C15") (pin "2") (pinfunction "2_2") (pintype "passive"))
      (node (ref "C16") (pin "2") (pinfunction "2_2") (pintype "passive"))
      (node (ref "C8") (pin "2") (pinfunction "2_2") (pintype "passive"))
      (node (ref "C9") (pin "2") (pinfunction "2_2") (pintype "passive"))
      (node (ref "P3") (pin "6") (pinfunction "6_6") (pintype "passive"))
      (node (ref "P4") (pin "1") (pinfunction "1_1") (pintype "passive"))
      (node (ref "Q1") (pin "2") (pinfunction "E_2") (pintype "passive"))
      (node (ref "Q2") (pin "3") (pinfunction "D_3") (pintype "passive"))
      (node (ref "Q3") (pin "3") (pinfunction "D_3") (pintype "passive"))
      (node (ref "Q4") (pin "3") (pinfunction "D_3") (pintype "passive"))
      (node (ref "Q5") (pin "3") (pinfunction "D_3") (pintype "passive"))
      (node (ref "R19") (pin "2") (pinfunction "2_2") (pintype "passive"))
      (node (ref "R21") (pin "1") (pinfunction "1_1") (pintype "passive"))
      (node (ref "R22") (pin "1") (pinfunction "1_1") (pintype "passive"))
      (node (ref "R27") (pin "2") (pinfunction "2_2") (pintype "passive"))
      (node (ref "R28") (pin "2") (pinfunction "2_2") (pintype "passive"))
      (node (ref "R29") (pin "2") (pinfunction "2_2") (pintype "passive"))
      (node (ref "R30") (pin "2") (pinfunction "2_2") (pintype "passive"))
      (node (ref "R6") (pin "2") (pinfunction "2_2") (pintype "passive"))
      (node (ref "U1") (pin "13") (pinfunction "VDDA_13") (pintype "power_in"))
      (node (ref "U1") (pin "19") (pinfunction "VDD_4_19") (pintype "power_in"))
      (node (ref "U1") (pin "32") (pinfunction "VDD_1_32") (pintype "power_in"))
      (node (ref "U1") (pin "48") (pinfunction "VDD_2_48") (pintype "power_in"))
      (node (ref "U1") (pin "64") (pinfunction "VDD_3_64") (pintype "power_in"))
      (node (ref "U3") (pin "8") (pinfunction "VCC_8") (pintype "power_in"))
      (node (ref "U4") (pin "8") (pinfunction "VCC_8") (pintype "power_in"))
    )
    (net (code "73") (name "unconnected-(U1-PB2{slash}BOOT1-Pad28)") (class "Default")
      (node (ref "U1") (pin "28") (pinfunction "PB2/BOOT1_28") (pintype "bidirectional"))
    )
  )
)
